# 01_powersupply.net
KiCad netlist of a schematic drawn in Altium Designer
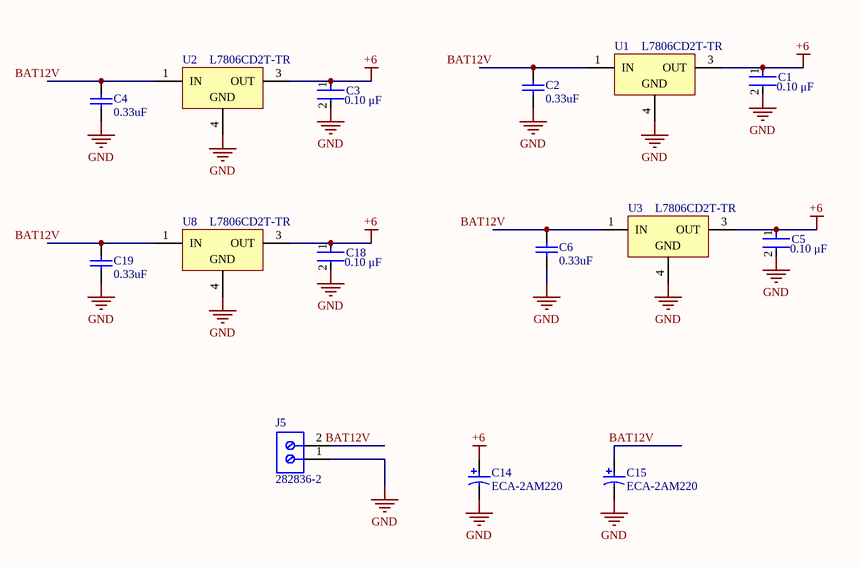
[diagram p0: 01_powersupply.SchDoc]

(export (version "E")
  (design (tool "Eeschema 10.0.6"))
  (components
    (comp (ref "C1")
      (value "C0603_0.1UF")
      (footprint "FP-C0603C-CF-MFG")
      (description "CAP CER 0.1UF 16V X7R 0603")
      (fields
        (field (name "TOLERANCE") "0.2")
        (field (name "CAPACITANCE") "0.10 μF")
        (field (name "MANUFACTURER PART NUMBER") "C0603C104M4RAC7411")
      )
      (libsource (lib "Altium Content Vault") (part "b4654b650e69147ec39a6b967a45e02"))
    )
    (comp (ref "C2")
      (value "0.33uF")
      (footprint "CAPC1608X90X20LL10")
      (description "Chip Capacitor, 0.33 uF, +/- 10%, 50 V, -55 to 125 degC, 0603 (1608 Metric), RoHS, Tape and Reel")
      (fields (field (name "MANUFACTURER") "TDK") (field (name "Comment") "C0603_0.33UF"))
      (libsource (lib "Altium Content Vault") (part "CAP-NP-2"))
    )
    (comp (ref "C3")
      (value "C0603_0.1UF")
      (footprint "FP-C0603C-CF-MFG")
      (description "CAP CER 0.1UF 16V X7R 0603")
      (fields
        (field (name "TOLERANCE") "0.2")
        (field (name "CAPACITANCE") "0.10 μF")
        (field (name "MANUFACTURER PART NUMBER") "C0603C104M4RAC7411")
      )
      (libsource (lib "Altium Content Vault") (part "b4654b650e69147ec39a6b967a45e02"))
    )
    (comp (ref "C4")
      (value "0.33uF")
      (footprint "CAPC1608X90X20LL10")
      (description "Chip Capacitor, 0.33 uF, +/- 10%, 50 V, -55 to 125 degC, 0603 (1608 Metric), RoHS, Tape and Reel")
      (fields (field (name "MANUFACTURER") "TDK") (field (name "Comment") "C0603_0.33UF"))
      (libsource (lib "Altium Content Vault") (part "CAP-NP-2"))
    )
    (comp (ref "C5")
      (value "C0603_0.1UF")
      (footprint "FP-C0603C-CF-MFG")
      (description "CAP CER 0.1UF 16V X7R 0603")
      (fields
        (field (name "TOLERANCE") "0.2")
        (field (name "CAPACITANCE") "0.10 μF")
        (field (name "MANUFACTURER PART NUMBER") "C0603C104M4RAC7411")
      )
      (libsource (lib "Altium Content Vault") (part "b4654b650e69147ec39a6b967a45e02"))
    )
    (comp (ref "C6")
      (value "0.33uF")
      (footprint "CAPC1608X90X20LL10")
      (description "Chip Capacitor, 0.33 uF, +/- 10%, 50 V, -55 to 125 degC, 0603 (1608 Metric), RoHS, Tape and Reel")
      (fields (field (name "MANUFACTURER") "TDK") (field (name "Comment") "C0603_0.33UF"))
      (libsource (lib "Altium Content Vault") (part "CAP-NP-2"))
    )
    (comp (ref "C14")
      (value "ECA-2AM220")
      (footprint "CAPPR55-250-1120X630X1220")
      (description "Aluminum Electrolytic Capacitor, 22 uF, +/- 20%, 100 V, -40 to 85 degC, 2-Pin THD, RoHS, Bulk")
      (libsource (lib "Altium Content Vault") (part "CAP-P-2"))
    )
    (comp (ref "C15")
      (value "ECA-2AM220")
      (footprint "CAPPR55-250-1120X630X1220")
      (description "Aluminum Electrolytic Capacitor, 22 uF, +/- 20%, 100 V, -40 to 85 degC, 2-Pin THD, RoHS, Bulk")
      (libsource (lib "Altium Content Vault") (part "CAP-P-2"))
    )
    (comp (ref "C18")
      (value "C0603_0.1UF")
      (footprint "FP-C0603C-CF-MFG")
      (description "CAP CER 0.1UF 16V X7R 0603")
      (fields
        (field (name "TOLERANCE") "0.2")
        (field (name "CAPACITANCE") "0.10 μF")
        (field (name "MANUFACTURER PART NUMBER") "C0603C104M4RAC7411")
      )
      (libsource (lib "Altium Content Vault") (part "b4654b650e69147ec39a6b967a45e02"))
    )
    (comp (ref "C19")
      (value "0.33uF")
      (footprint "CAPC1608X90X20LL10")
      (description "Chip Capacitor, 0.33 uF, +/- 10%, 50 V, -55 to 125 degC, 0603 (1608 Metric), RoHS, Tape and Reel")
      (fields (field (name "MANUFACTURER") "TDK") (field (name "Comment") "C0603_0.33UF"))
      (libsource (lib "Altium Content Vault") (part "CAP-NP-2"))
    )
    (comp (ref "J5")
      (value "282836-2")
      (footprint "TECO-282836-2_V")
      (description "Female Header, Pitch 5 mm, 1 x 2 Position, Height 10 mm, Tail Length 3.5 mm, Rohs, Bulk")
      (fields (field (name "VOLTAGE") "300V") (field (name "MANUFACTURER") "TE Connectivity"))
      (libsource (lib "Altium Content Vault") (part "CN-1P-F-TB2"))
    )
    (comp (ref "U1")
      (value "L7806CD2T-TR")
      (footprint "TO-263_L")
      (description "Positive Voltage Regulator, 3-Pin D2PAK, Tape and Reel")
      (libsource (lib "Altium Content Vault") (part "PM-REG-L4940-SOT3"))
    )
    (comp (ref "U2")
      (value "L7806CD2T-TR")
      (footprint "TO-263_L")
      (description "Positive Voltage Regulator, 3-Pin D2PAK, Tape and Reel")
      (libsource (lib "Altium Content Vault") (part "PM-REG-L4940-SOT3"))
    )
    (comp (ref "U3")
      (value "L7806CD2T-TR")
      (footprint "TO-263_L")
      (description "Positive Voltage Regulator, 3-Pin D2PAK, Tape and Reel")
      (libsource (lib "Altium Content Vault") (part "PM-REG-L4940-SOT3"))
    )
    (comp (ref "U8")
      (value "L7806CD2T-TR")
      (footprint "TO-263_L")
      (description "Positive Voltage Regulator, 3-Pin D2PAK, Tape and Reel")
      (libsource (lib "Altium Content Vault") (part "PM-REG-L4940-SOT3"))
    )
  )
  (nets
    (net (code "1") (name "+6") (class "Default")
      (node (ref "C1") (pin "1") (pinfunction "1_1") (pintype "passive"))
      (node (ref "C14") (pin "1") (pinfunction "1_1") (pintype "passive"))
      (node (ref "C18") (pin "1") (pinfunction "1_1") (pintype "passive"))
      (node (ref "C3") (pin "1") (pinfunction "1_1") (pintype "passive"))
      (node (ref "C5") (pin "1") (pinfunction "1_1") (pintype "passive"))
      (node (ref "U1") (pin "3") (pinfunction "OUT_3") (pintype "power_in"))
      (node (ref "U2") (pin "3") (pinfunction "OUT_3") (pintype "power_in"))
      (node (ref "U3") (pin "3") (pinfunction "OUT_3") (pintype "power_in"))
      (node (ref "U8") (pin "3") (pinfunction "OUT_3") (pintype "power_in"))
    )
    (net (code "2") (name "/BAT12V") (class "Default")
      (node (ref "C15") (pin "1") (pinfunction "1_1") (pintype "passive"))
      (node (ref "C19") (pin "2") (pinfunction "2_2") (pintype "passive"))
      (node (ref "C2") (pin "2") (pinfunction "2_2") (pintype "passive"))
      (node (ref "C4") (pin "2") (pinfunction "2_2") (pintype "passive"))
      (node (ref "C6") (pin "2") (pinfunction "2_2") (pintype "passive"))
      (node (ref "J5") (pin "2") (pinfunction "2_2") (pintype "passive"))
      (node (ref "U1") (pin "1") (pinfunction "IN_1") (pintype "power_in"))
      (node (ref "U2") (pin "1") (pinfunction "IN_1") (pintype "power_in"))
      (node (ref "U3") (pin "1") (pinfunction "IN_1") (pintype "power_in"))
      (node (ref "U8") (pin "1") (pinfunction "IN_1") (pintype "power_in"))
    )
    (net (code "3") (name "GND") (class "Default")
      (node (ref "C1") (pin "2") (pinfunction "2_2") (pintype "passive"))
      (node (ref "C14") (pin "2") (pinfunction "2_2") (pintype "passive"))
      (node (ref "C15") (pin "2") (pinfunction "2_2") (pintype "passive"))
      (node (ref "C18") (pin "2") (pinfunction "2_2") (pintype "passive"))
      (node (ref "C19") (pin "1") (pinfunction "1_1") (pintype "passive"))
      (node (ref "C2") (pin "1") (pinfunction "1_1") (pintype "passive"))
      (node (ref "C3") (pin "2") (pinfunction "2_2") (pintype "passive"))
      (node (ref "C4") (pin "1") (pinfunction "1_1") (pintype "passive"))
      (node (ref "C5") (pin "2") (pinfunction "2_2") (pintype "passive"))
      (node (ref "C6") (pin "1") (pinfunction "1_1") (pintype "passive"))
      (node (ref "J5") (pin "1") (pinfunction "1_1") (pintype "passive"))
      (node (ref "U1") (pin "4") (pinfunction "GND_4") (pintype "power_in"))
      (node (ref "U2") (pin "4") (pinfunction "GND_4") (pintype "power_in"))
      (node (ref "U3") (pin "4") (pinfunction "GND_4") (pintype "power_in"))
      (node (ref "U8") (pin "4") (pinfunction "GND_4") (pintype "power_in"))
    )
  )
)
